# 5uH_LISN.net
KiCad netlist of a schematic drawn in EAGLE
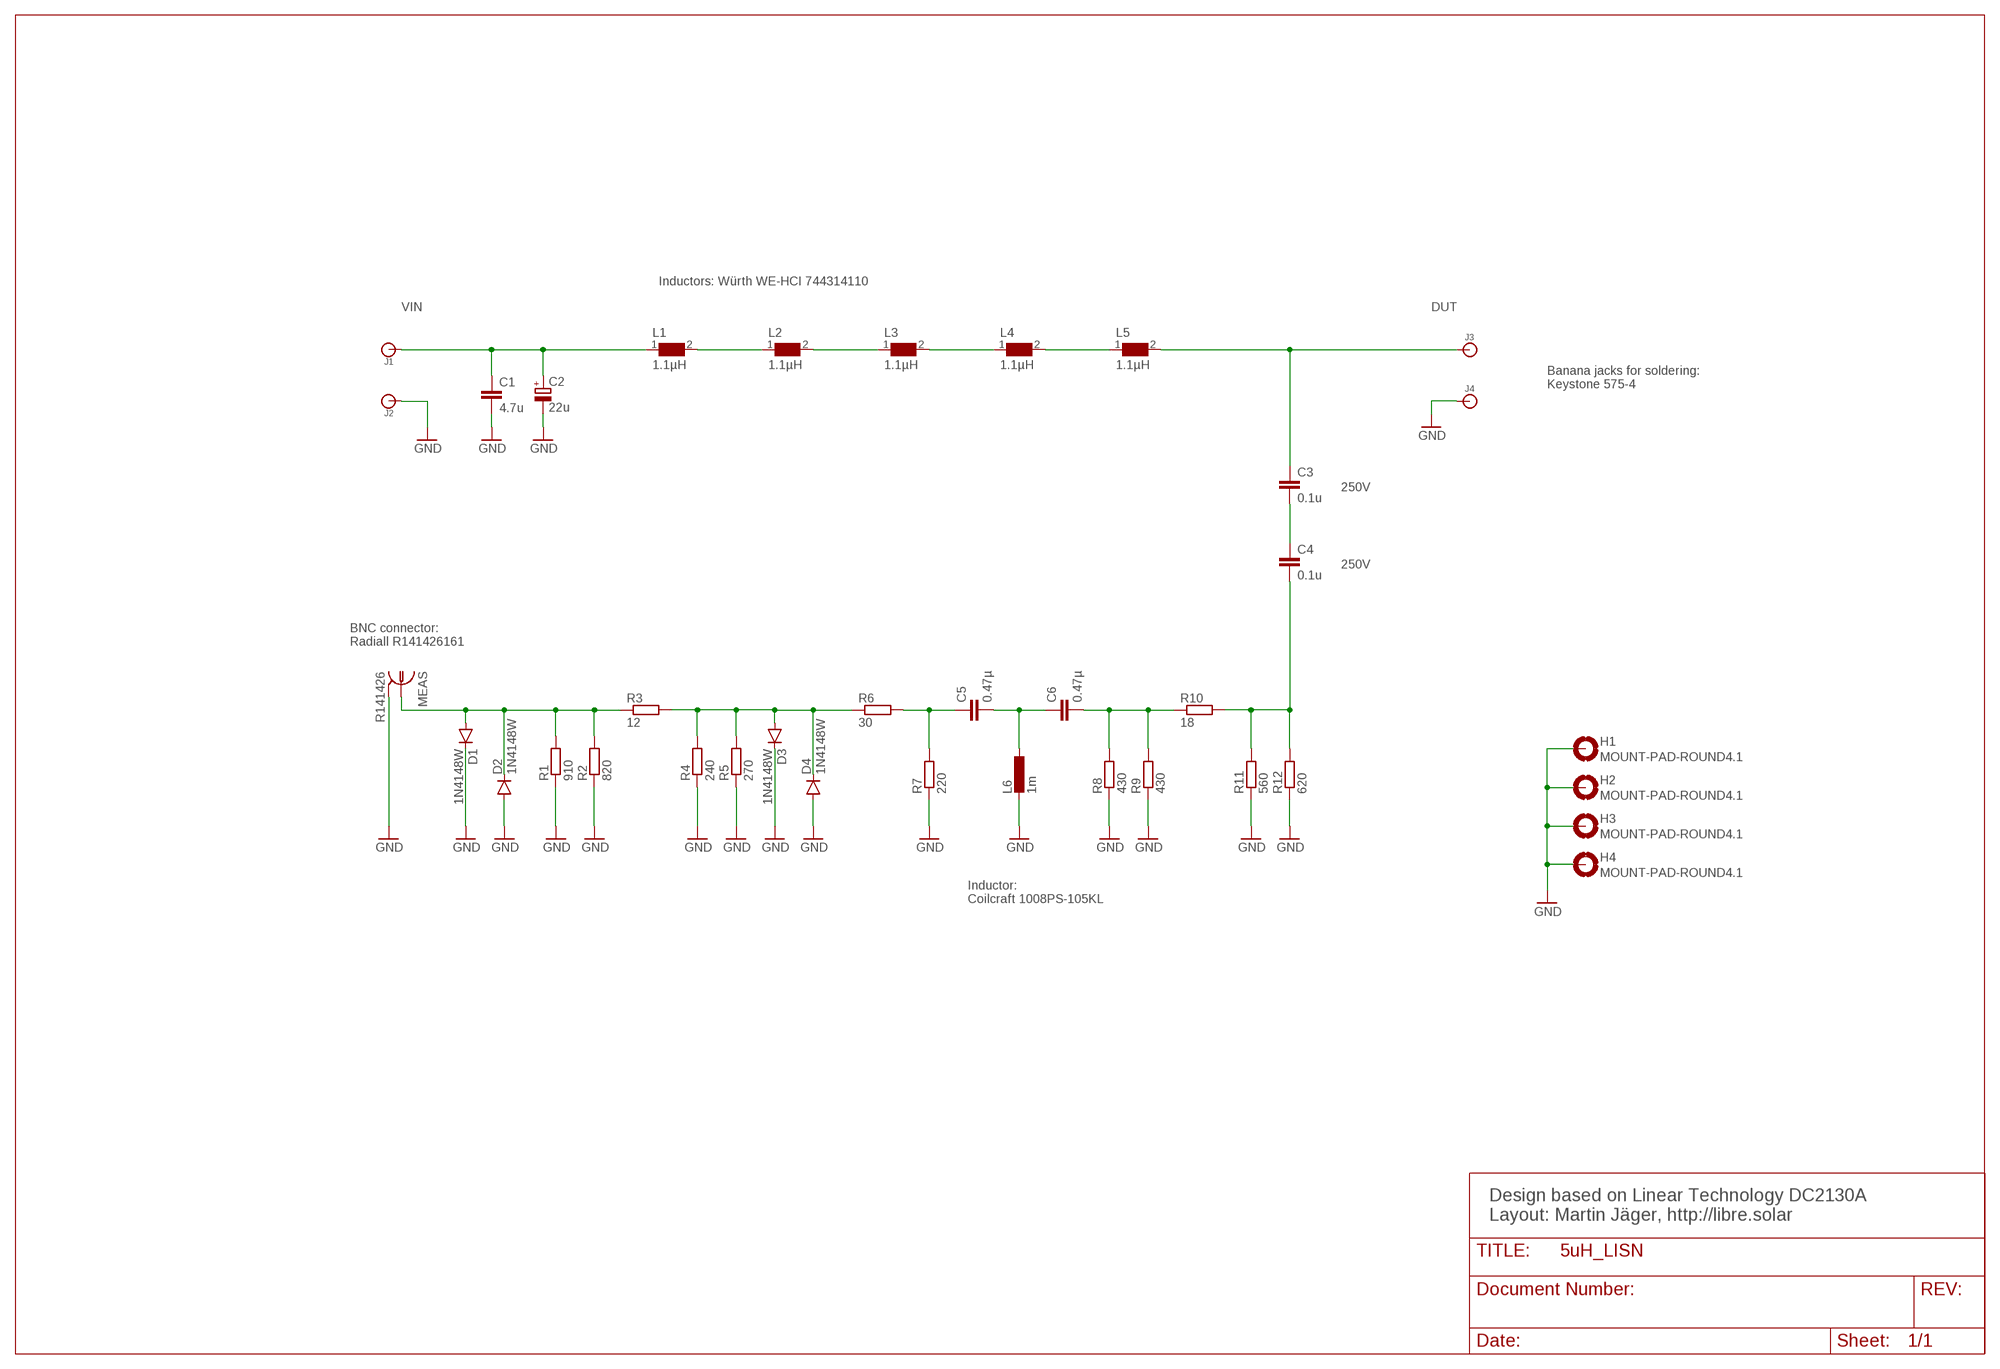
[diagram p0: schematic, sheet 1]

(export (version "E")
  (design (tool "Eeschema 10.0.6"))
  (components
    (comp (ref "C1")
      (value "4.7u")
      (footprint "eagle-import:C1210")
      (libsource (lib "eagle-import") (part "C-EUC1210"))
    )
    (comp (ref "C2")
      (value "22u")
      (footprint "eagle-import:PANASONIC_B")
      (libsource (lib "eagle-import") (part "CPOL-EUB"))
    )
    (comp (ref "C3")
      (value "0.1u")
      (footprint "eagle-import:C1206")
      (libsource (lib "eagle-import") (part "C-EUC1206"))
    )
    (comp (ref "C4")
      (value "0.1u")
      (footprint "eagle-import:C1206")
      (libsource (lib "eagle-import") (part "C-EUC1206"))
    )
    (comp (ref "C5")
      (value "0.47µ")
      (footprint "eagle-import:C0805")
      (libsource (lib "eagle-import") (part "C-EUC0805"))
    )
    (comp (ref "C6")
      (value "0.47µ")
      (footprint "eagle-import:C0805")
      (libsource (lib "eagle-import") (part "C-EUC0805"))
    )
    (comp (ref "D1")
      (value "1N4148W")
      (footprint "eagle-import:SOD-123")
      (fields (field (name "MF") "DIODES INC.") (field (name "MPN") "1N4148W-7-F."))
      (libsource (lib "eagle-import") (part "DIODESOD123"))
    )
    (comp (ref "D2")
      (value "1N4148W")
      (footprint "eagle-import:SOD-123")
      (fields (field (name "MF") "DIODES INC.") (field (name "MPN") "1N4148W-7-F."))
      (libsource (lib "eagle-import") (part "DIODESOD123"))
    )
    (comp (ref "D3")
      (value "1N4148W")
      (footprint "eagle-import:SOD-123")
      (fields (field (name "MF") "DIODES INC.") (field (name "MPN") "1N4148W-7-F."))
      (libsource (lib "eagle-import") (part "DIODESOD123"))
    )
    (comp (ref "D4")
      (value "1N4148W")
      (footprint "eagle-import:SOD-123")
      (fields (field (name "MF") "DIODES INC.") (field (name "MPN") "1N4148W-7-F."))
      (libsource (lib "eagle-import") (part "DIODESOD123"))
    )
    (comp (ref "H1")
      (value "MOUNT-PAD-ROUND4.1")
      (footprint "eagle-import:4,1-PAD")
      (libsource (lib "eagle-import") (part "MOUNT-PAD-ROUND4.1"))
    )
    (comp (ref "H2")
      (value "MOUNT-PAD-ROUND4.1")
      (footprint "eagle-import:4,1-PAD")
      (libsource (lib "eagle-import") (part "MOUNT-PAD-ROUND4.1"))
    )
    (comp (ref "H3")
      (value "MOUNT-PAD-ROUND4.1")
      (footprint "eagle-import:4,1-PAD")
      (libsource (lib "eagle-import") (part "MOUNT-PAD-ROUND4.1"))
    )
    (comp (ref "H4")
      (value "MOUNT-PAD-ROUND4.1")
      (footprint "eagle-import:4,1-PAD")
      (libsource (lib "eagle-import") (part "MOUNT-PAD-ROUND4.1"))
    )
    (comp (ref "J1")
      (value "BANANA_CONN")
      (footprint "eagle-import:BANANA_CONN")
      (libsource (lib "eagle-import") (part "BANANA_CONN"))
    )
    (comp (ref "J2")
      (value "BANANA_CONN")
      (footprint "eagle-import:BANANA_CONN")
      (libsource (lib "eagle-import") (part "BANANA_CONN"))
    )
    (comp (ref "J3")
      (value "BANANA_CONN")
      (footprint "eagle-import:BANANA_CONN")
      (libsource (lib "eagle-import") (part "BANANA_CONN"))
    )
    (comp (ref "J4")
      (value "BANANA_CONN")
      (footprint "eagle-import:BANANA_CONN")
      (libsource (lib "eagle-import") (part "BANANA_CONN"))
    )
    (comp (ref "L1")
      (value "1.1µH")
      (footprint "eagle-import:WE-HCI_7030_7040_7050")
      (libsource (lib "eagle-import") (part "WE-HCI_7030/7040/7050"))
    )
    (comp (ref "L2")
      (value "1.1µH")
      (footprint "eagle-import:WE-HCI_7030_7040_7050")
      (libsource (lib "eagle-import") (part "WE-HCI_7030/7040/7050"))
    )
    (comp (ref "L3")
      (value "1.1µH")
      (footprint "eagle-import:WE-HCI_7030_7040_7050")
      (libsource (lib "eagle-import") (part "WE-HCI_7030/7040/7050"))
    )
    (comp (ref "L4")
      (value "1.1µH")
      (footprint "eagle-import:WE-HCI_7030_7040_7050")
      (libsource (lib "eagle-import") (part "WE-HCI_7030/7040/7050"))
    )
    (comp (ref "L5")
      (value "1.1µH")
      (footprint "eagle-import:WE-HCI_7030_7040_7050")
      (libsource (lib "eagle-import") (part "WE-HCI_7030/7040/7050"))
    )
    (comp (ref "L6")
      (value "1m")
      (footprint "eagle-import:COILCRAFT_1008PS")
      (libsource (lib "eagle-import") (part "INDUCTOR"))
    )
    (comp (ref "MEAS")
      (value "R141426")
      (footprint "eagle-import:R141426")
      (fields (field (name "MF") "FARNELL") (field (name "MPN") "R141426161"))
      (libsource (lib "eagle-import") (part "R141426"))
    )
    (comp (ref "R1")
      (value "910")
      (footprint "eagle-import:R0805")
      (libsource (lib "eagle-import") (part "R-EU_R0805"))
    )
    (comp (ref "R2")
      (value "820")
      (footprint "eagle-import:R0805")
      (libsource (lib "eagle-import") (part "R-EU_R0805"))
    )
    (comp (ref "R3")
      (value "12")
      (footprint "eagle-import:R0805")
      (libsource (lib "eagle-import") (part "R-EU_R0805"))
    )
    (comp (ref "R4")
      (value "240")
      (footprint "eagle-import:R0805")
      (libsource (lib "eagle-import") (part "R-EU_R0805"))
    )
    (comp (ref "R5")
      (value "270")
      (footprint "eagle-import:R0805")
      (libsource (lib "eagle-import") (part "R-EU_R0805"))
    )
    (comp (ref "R6")
      (value "30")
      (footprint "eagle-import:R0805")
      (libsource (lib "eagle-import") (part "R-EU_R0805"))
    )
    (comp (ref "R7")
      (value "220")
      (footprint "eagle-import:R0805")
      (libsource (lib "eagle-import") (part "R-EU_R0805"))
    )
    (comp (ref "R8")
      (value "430")
      (footprint "eagle-import:R0805")
      (libsource (lib "eagle-import") (part "R-EU_R0805"))
    )
    (comp (ref "R9")
      (value "430")
      (footprint "eagle-import:R0805")
      (libsource (lib "eagle-import") (part "R-EU_R0805"))
    )
    (comp (ref "R10")
      (value "18")
      (footprint "eagle-import:R0805")
      (libsource (lib "eagle-import") (part "R-EU_R0805"))
    )
    (comp (ref "R11")
      (value "560")
      (footprint "eagle-import:R0805")
      (libsource (lib "eagle-import") (part "R-EU_R0805"))
    )
    (comp (ref "R12")
      (value "620")
      (footprint "eagle-import:R0805")
      (libsource (lib "eagle-import") (part "R-EU_R0805"))
    )
  )
  (nets
    (net (code "1") (name "GND") (class "Default")
      (node (ref "C1") (pin "2") (pinfunction "2_2") (pintype "passive"))
      (node (ref "C2") (pin "-") (pinfunction "-_-") (pintype "passive"))
      (node (ref "D1") (pin "C") (pinfunction "C_C") (pintype "passive"))
      (node (ref "D2") (pin "A") (pinfunction "A_A") (pintype "passive"))
      (node (ref "D3") (pin "C") (pinfunction "C_C") (pintype "passive"))
      (node (ref "D4") (pin "A") (pinfunction "A_A") (pintype "passive"))
      (node (ref "H1") (pin "B4,1") (pinfunction "MOUNT_B4,1") (pintype "passive"))
      (node (ref "H2") (pin "B4,1") (pinfunction "MOUNT_B4,1") (pintype "passive"))
      (node (ref "H3") (pin "B4,1") (pinfunction "MOUNT_B4,1") (pintype "passive"))
      (node (ref "H4") (pin "B4,1") (pinfunction "MOUNT_B4,1") (pintype "passive"))
      (node (ref "J2") (pin "P$1") (pinfunction "1_P$1") (pintype "passive"))
      (node (ref "J4") (pin "P$1") (pinfunction "1_P$1") (pintype "passive"))
      (node (ref "L6") (pin "P$2") (pinfunction "2_P$2") (pintype "passive"))
      (node (ref "MEAS") (pin "2") (pinfunction "2_2") (pintype "passive"))
      (node (ref "MEAS") (pin "3") (pinfunction "2_3") (pintype "passive"))
      (node (ref "MEAS") (pin "4") (pinfunction "2_4") (pintype "passive"))
      (node (ref "MEAS") (pin "5") (pinfunction "2_5") (pintype "passive"))
      (node (ref "R1") (pin "1") (pinfunction "1_1") (pintype "passive"))
      (node (ref "R11") (pin "1") (pinfunction "1_1") (pintype "passive"))
      (node (ref "R12") (pin "1") (pinfunction "1_1") (pintype "passive"))
      (node (ref "R2") (pin "1") (pinfunction "1_1") (pintype "passive"))
      (node (ref "R4") (pin "1") (pinfunction "1_1") (pintype "passive"))
      (node (ref "R5") (pin "1") (pinfunction "1_1") (pintype "passive"))
      (node (ref "R7") (pin "1") (pinfunction "1_1") (pintype "passive"))
      (node (ref "R8") (pin "1") (pinfunction "1_1") (pintype "passive"))
      (node (ref "R9") (pin "1") (pinfunction "1_1") (pintype "passive"))
    )
    (net (code "2") (name "Net-(C3-Pad2)") (class "Default")
      (node (ref "C3") (pin "2") (pinfunction "2_2") (pintype "passive"))
      (node (ref "C4") (pin "1") (pinfunction "1_1") (pintype "passive"))
    )
    (net (code "3") (name "Net-(C4-Pad2)") (class "Default")
      (node (ref "C4") (pin "2") (pinfunction "2_2") (pintype "passive"))
      (node (ref "R10") (pin "2") (pinfunction "2_2") (pintype "passive"))
      (node (ref "R11") (pin "2") (pinfunction "2_2") (pintype "passive"))
      (node (ref "R12") (pin "2") (pinfunction "2_2") (pintype "passive"))
    )
    (net (code "4") (name "Net-(C5-Pad1)") (class "Default")
      (node (ref "C5") (pin "1") (pinfunction "1_1") (pintype "passive"))
      (node (ref "R6") (pin "2") (pinfunction "2_2") (pintype "passive"))
      (node (ref "R7") (pin "2") (pinfunction "2_2") (pintype "passive"))
    )
    (net (code "5") (name "Net-(C6-Pad2)") (class "Default")
      (node (ref "C6") (pin "2") (pinfunction "2_2") (pintype "passive"))
      (node (ref "R10") (pin "1") (pinfunction "1_1") (pintype "passive"))
      (node (ref "R8") (pin "2") (pinfunction "2_2") (pintype "passive"))
      (node (ref "R9") (pin "2") (pinfunction "2_2") (pintype "passive"))
    )
    (net (code "6") (name "Net-(D1-PadA)") (class "Default")
      (node (ref "D1") (pin "A") (pinfunction "A_A") (pintype "passive"))
      (node (ref "D2") (pin "C") (pinfunction "C_C") (pintype "passive"))
      (node (ref "MEAS") (pin "1") (pinfunction "1_1") (pintype "passive"))
      (node (ref "R1") (pin "2") (pinfunction "2_2") (pintype "passive"))
      (node (ref "R2") (pin "2") (pinfunction "2_2") (pintype "passive"))
      (node (ref "R3") (pin "1") (pinfunction "1_1") (pintype "passive"))
    )
    (net (code "7") (name "Net-(D3-PadA)") (class "Default")
      (node (ref "D3") (pin "A") (pinfunction "A_A") (pintype "passive"))
      (node (ref "D4") (pin "C") (pinfunction "C_C") (pintype "passive"))
      (node (ref "R3") (pin "2") (pinfunction "2_2") (pintype "passive"))
      (node (ref "R4") (pin "2") (pinfunction "2_2") (pintype "passive"))
      (node (ref "R5") (pin "2") (pinfunction "2_2") (pintype "passive"))
      (node (ref "R6") (pin "1") (pinfunction "1_1") (pintype "passive"))
    )
    (net (code "8") (name "Net-(J1-1)") (class "Default")
      (node (ref "C1") (pin "1") (pinfunction "1_1") (pintype "passive"))
      (node (ref "C2") (pin "+") (pinfunction "+_+") (pintype "passive"))
      (node (ref "J1") (pin "P$1") (pinfunction "1_P$1") (pintype "passive"))
      (node (ref "L1") (pin "1") (pinfunction "1_1") (pintype "passive"))
    )
    (net (code "9") (name "Net-(J3-1)") (class "Default")
      (node (ref "C3") (pin "1") (pinfunction "1_1") (pintype "passive"))
      (node (ref "J3") (pin "P$1") (pinfunction "1_P$1") (pintype "passive"))
      (node (ref "L5") (pin "2") (pinfunction "2_2") (pintype "passive"))
    )
    (net (code "10") (name "Net-(L1-Pad2)") (class "Default")
      (node (ref "L1") (pin "2") (pinfunction "2_2") (pintype "passive"))
      (node (ref "L2") (pin "1") (pinfunction "1_1") (pintype "passive"))
    )
    (net (code "11") (name "Net-(L2-Pad2)") (class "Default")
      (node (ref "L2") (pin "2") (pinfunction "2_2") (pintype "passive"))
      (node (ref "L3") (pin "1") (pinfunction "1_1") (pintype "passive"))
    )
    (net (code "12") (name "Net-(L3-Pad2)") (class "Default")
      (node (ref "L3") (pin "2") (pinfunction "2_2") (pintype "passive"))
      (node (ref "L4") (pin "1") (pinfunction "1_1") (pintype "passive"))
    )
    (net (code "13") (name "Net-(L4-Pad2)") (class "Default")
      (node (ref "L4") (pin "2") (pinfunction "2_2") (pintype "passive"))
      (node (ref "L5") (pin "1") (pinfunction "1_1") (pintype "passive"))
    )
    (net (code "14") (name "Net-(L6-1)") (class "Default")
      (node (ref "C5") (pin "2") (pinfunction "2_2") (pintype "passive"))
      (node (ref "C6") (pin "1") (pinfunction "1_1") (pintype "passive"))
      (node (ref "L6") (pin "P$1") (pinfunction "1_P$1") (pintype "passive"))
    )
  )
)
